# 1st-project.net
KiCad netlist of a schematic drawn in EAGLE
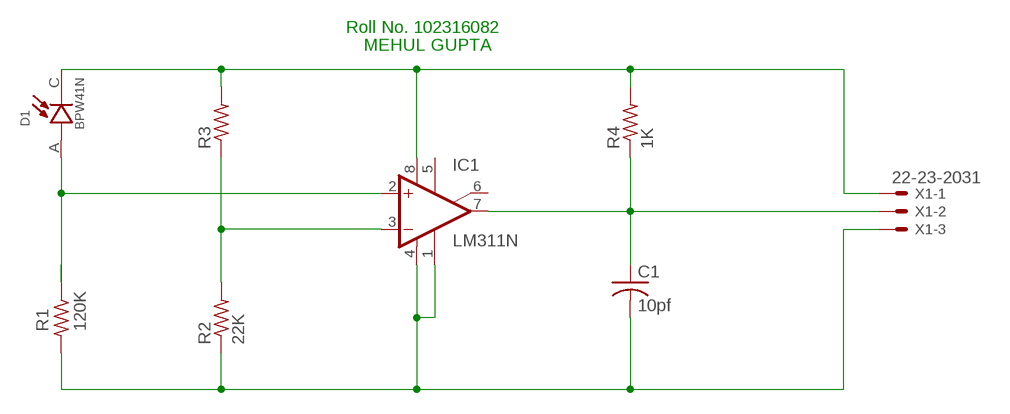
[diagram p0: schematic, sheet 1]

(export (version "E")
  (design (tool "Eeschema 10.0.6"))
  (components
    (comp (ref "C1")
      (value "10pf")
      (footprint "eagle-import:C025-024X044")
      (libsource (lib "eagle-import") (part "C-US025-024X044"))
    )
    (comp (ref "D1")
      (value "BPW41N")
      (footprint "eagle-import:DIO_BPW41N")
      (fields (field (name "MF") "Vishay Semiconductor Opto Division"))
      (libsource (lib "eagle-import") (part "BPW41N"))
    )
    (comp (ref "IC1")
      (value "LM311N")
      (footprint "eagle-import:DIL08")
      (libsource (lib "eagle-import") (part "LM311N"))
    )
    (comp (ref "R1")
      (value "120K")
      (footprint "eagle-import:0204_5")
      (libsource (lib "eagle-import") (part "R-US_0204/5"))
    )
    (comp (ref "R2")
      (value "22K")
      (footprint "eagle-import:0204_5")
      (libsource (lib "eagle-import") (part "R-US_0204/5"))
    )
    (comp (ref "R3")
      (value "R-US_0204/5")
      (footprint "eagle-import:0204_5")
      (libsource (lib "eagle-import") (part "R-US_0204/5"))
    )
    (comp (ref "R4")
      (value "1K")
      (footprint "eagle-import:0204_5")
      (libsource (lib "eagle-import") (part "R-US_0204/5"))
    )
    (comp (ref "X1")
      (value "22-23-2031")
      (footprint "eagle-import:22-23-2031")
      (fields (field (name "MF") "MOLEX"))
      (libsource (lib "eagle-import") (part "22-23-2031"))
    )
  )
  (nets
    (net (code "1") (name "Net-(IC1-+IN)") (class "Default")
      (node (ref "D1") (pin "A") (pinfunction "A_A") (pintype "passive"))
      (node (ref "IC1") (pin "2") (pinfunction "+IN_2") (pintype "input"))
      (node (ref "R1") (pin "1") (pinfunction "1_1") (pintype "passive"))
    )
    (net (code "2") (name "Net-(IC1--IN)") (class "Default")
      (node (ref "IC1") (pin "3") (pinfunction "-IN_3") (pintype "input"))
      (node (ref "R2") (pin "2") (pinfunction "2_2") (pintype "passive"))
      (node (ref "R3") (pin "1") (pinfunction "1_1") (pintype "passive"))
    )
    (net (code "3") (name "Net-(IC1-GND)") (class "Default")
      (node (ref "C1") (pin "2") (pinfunction "2_2") (pintype "passive"))
      (node (ref "IC1") (pin "1") (pinfunction "GND_1") (pintype "passive"))
      (node (ref "IC1") (pin "4") (pinfunction "V-_4") (pintype "power_in"))
      (node (ref "R1") (pin "2") (pinfunction "2_2") (pintype "passive"))
      (node (ref "R2") (pin "1") (pinfunction "1_1") (pintype "passive"))
      (node (ref "X1") (pin "3") (pinfunction "S_3") (pintype "passive"))
    )
    (net (code "4") (name "Net-(IC1-OUT)") (class "Default")
      (node (ref "C1") (pin "1") (pinfunction "1_1") (pintype "passive"))
      (node (ref "IC1") (pin "7") (pinfunction "OUT_7") (pintype "output"))
      (node (ref "R4") (pin "1") (pinfunction "1_1") (pintype "passive"))
      (node (ref "X1") (pin "2") (pinfunction "S_2") (pintype "passive"))
    )
    (net (code "5") (name "Net-(IC1-V+)") (class "Default")
      (node (ref "D1") (pin "C") (pinfunction "C_C") (pintype "passive"))
      (node (ref "IC1") (pin "8") (pinfunction "V+_8") (pintype "power_in"))
      (node (ref "R3") (pin "2") (pinfunction "2_2") (pintype "passive"))
      (node (ref "R4") (pin "2") (pinfunction "2_2") (pintype "passive"))
      (node (ref "X1") (pin "1") (pinfunction "S_1") (pintype "passive"))
    )
    (net (code "6") (name "unconnected-(IC1-ON-Pad5)") (class "Default")
      (node (ref "IC1") (pin "5") (pinfunction "ON_5") (pintype "passive"))
    )
    (net (code "7") (name "unconnected-(IC1-ON{slash}STR-Pad6)") (class "Default")
      (node (ref "IC1") (pin "6") (pinfunction "ON/STR_6") (pintype "passive"))
    )
  )
)
